# MSD.net
KiCad netlist of a schematic drawn in Altium Designer
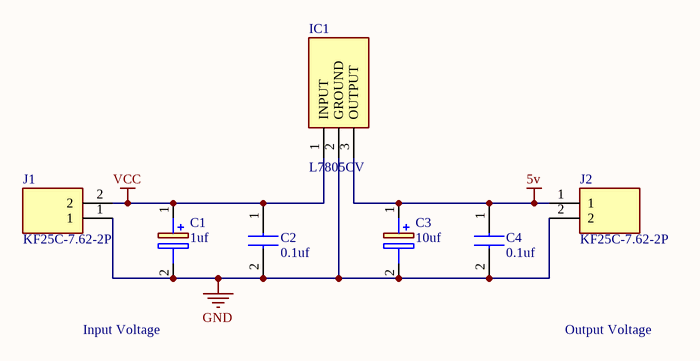
[diagram p0: MSD.SchDoc]

(export (version "E")
  (design (tool "Eeschema 10.0.6"))
  (components
    (comp (ref "C1")
      (value "1uf")
      (footprint "SamacSys:CAPPRD350W65D825H1250")
      (description "Capacitor Polarised")
      (fields
        (field (name "MANUFACTURER_PART_NUMBER") "ECA-2WM010")
        (field (name "MOUSER PART NUMBER") "667-ECA-2WM010")
      )
      (libsource (lib "SamacSys") (part "ECA-2WM010"))
    )
    (comp (ref "C2")
      (value "0.1uf")
      (footprint "SamacSys:CAPPRD200W50D550H1250")
      (description "Capacitor")
      (fields
        (field (name "MANUFACTURER_PART_NUMBER") "UPS1H010MDD")
        (field (name "MOUSER PART NUMBER") "647-UPS1H010MDD")
      )
      (libsource (lib "SamacSys") (part "UPS1H010MDD"))
    )
    (comp (ref "C3")
      (value "10uf")
      (footprint "SamacSys:CAPPRD500W65D1000H2200")
      (description "Capacitor Polarised")
      (fields
        (field (name "MANUFACTURER_PART_NUMBER") "EEU-EB2V100")
        (field (name "MOUSER PART NUMBER") "667-EEU-EB2V100")
      )
      (libsource (lib "SamacSys") (part "EEU-EB2V100"))
    )
    (comp (ref "C4")
      (value "0.1uf")
      (footprint "SamacSys:CAPPRD200W50D550H1250")
      (description "Capacitor")
      (fields
        (field (name "MANUFACTURER_PART_NUMBER") "UPS1H010MDD")
        (field (name "MOUSER PART NUMBER") "647-UPS1H010MDD")
      )
      (libsource (lib "SamacSys") (part "UPS1H010MDD"))
    )
    (comp (ref "IC1")
      (value "L7805CV")
      (footprint "SamacSys:TO255P460X1020X2008-3P")
      (description "Integrated Circuit")
      (fields (field (name "MOUSER PART NUMBER") "511-L7805CV"))
      (libsource (lib "SamacSys") (part "L7805CV"))
    )
    (comp (ref "J1")
      (value "KF25C-7.62-2P")
      (footprint "SamacSys:KF25C7622P")
      (description "Connector")
      (libsource (lib "") (part "KF25C-7.62-2P_1"))
    )
    (comp (ref "J2")
      (value "KF25C-7.62-2P")
      (footprint "SamacSys:KF25C7622P")
      (description "Connector")
      (libsource (lib "SamacSys") (part "KF25C-7.62-2P"))
    )
  )
  (nets
    (net (code "1") (name "5v") (class "Default")
      (node (ref "C3") (pin "1") (pinfunction "+_1") (pintype "passive"))
      (node (ref "C4") (pin "1") (pinfunction "+_1") (pintype "passive"))
      (node (ref "IC1") (pin "3") (pinfunction "OUTPUT_3") (pintype "passive"))
      (node (ref "J2") (pin "1") (pinfunction "1_1") (pintype "passive"))
    )
    (net (code "2") (name "GND") (class "Default")
      (node (ref "C1") (pin "2") (pinfunction "-_2") (pintype "passive"))
      (node (ref "C2") (pin "2") (pinfunction "-_2") (pintype "passive"))
      (node (ref "C3") (pin "2") (pinfunction "-_2") (pintype "passive"))
      (node (ref "C4") (pin "2") (pinfunction "-_2") (pintype "passive"))
      (node (ref "IC1") (pin "2") (pinfunction "GROUND_2") (pintype "passive"))
      (node (ref "J1") (pin "1") (pinfunction "1_1") (pintype "passive"))
      (node (ref "J2") (pin "2") (pinfunction "2_2") (pintype "passive"))
    )
    (net (code "3") (name "VCC") (class "Default")
      (node (ref "C1") (pin "1") (pinfunction "+_1") (pintype "passive"))
      (node (ref "C2") (pin "1") (pinfunction "+_1") (pintype "passive"))
      (node (ref "IC1") (pin "1") (pinfunction "INPUT_1") (pintype "passive"))
      (node (ref "J1") (pin "2") (pinfunction "2_2") (pintype "passive"))
    )
  )
)
